# 11Dof.net
KiCad netlist of a schematic drawn in EAGLE
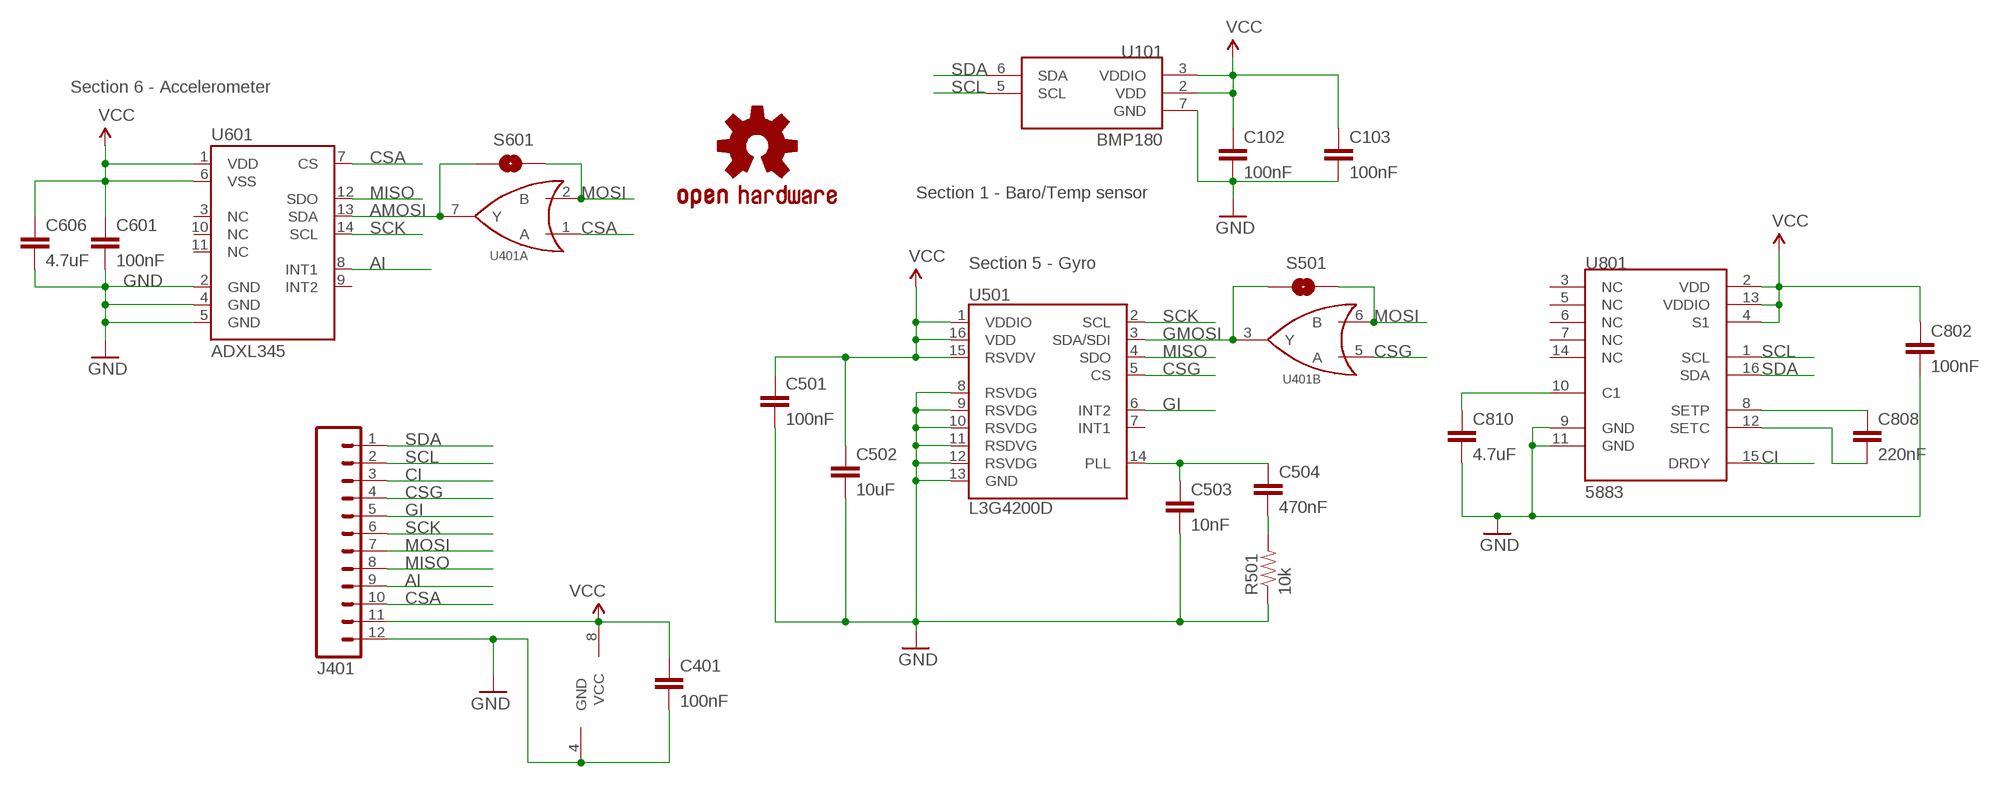
[diagram p0: schematic, sheet 1]

(export (version "E")
  (design (tool "Eeschema 10.0.6"))
  (components
    (comp (ref "C102")
      (value "100nF")
      (footprint "eagle-import:0603-CAP")
      (libsource (lib "eagle-import") (part "CAP0603-CAP"))
    )
    (comp (ref "C103")
      (value "100nF")
      (footprint "eagle-import:0603-CAP")
      (libsource (lib "eagle-import") (part "CAP0603-CAP"))
    )
    (comp (ref "C401")
      (value "100nF")
      (footprint "eagle-import:0603-CAP")
      (libsource (lib "eagle-import") (part "CAP0603-CAP"))
    )
    (comp (ref "C501")
      (value "100nF")
      (footprint "eagle-import:0603-CAP")
      (libsource (lib "eagle-import") (part "CAP0603-CAP"))
    )
    (comp (ref "C502")
      (value "10uF")
      (footprint "eagle-import:0603-CAP")
      (libsource (lib "eagle-import") (part "CAP0603-CAP"))
    )
    (comp (ref "C503")
      (value "10nF")
      (footprint "eagle-import:0603-CAP")
      (libsource (lib "eagle-import") (part "CAP0603-CAP"))
    )
    (comp (ref "C504")
      (value "470nF")
      (footprint "eagle-import:0603-CAP")
      (libsource (lib "eagle-import") (part "CAP0603-CAP"))
    )
    (comp (ref "C601")
      (value "100nF")
      (footprint "eagle-import:0603-CAP")
      (libsource (lib "eagle-import") (part "CAP0603-CAP"))
    )
    (comp (ref "C606")
      (value "4.7uF")
      (footprint "eagle-import:0603-CAP")
      (libsource (lib "eagle-import") (part "CAP0603-CAP"))
    )
    (comp (ref "C802")
      (value "100nF")
      (footprint "eagle-import:0603-CAP")
      (libsource (lib "eagle-import") (part "CAP0603-CAP"))
    )
    (comp (ref "C808")
      (value "220nF")
      (footprint "eagle-import:0603-CAP")
      (libsource (lib "eagle-import") (part "CAP0603-CAP"))
    )
    (comp (ref "C810")
      (value "4.7uF")
      (footprint "eagle-import:0603-CAP")
      (libsource (lib "eagle-import") (part "CAP0603-CAP"))
    )
    (comp (ref "J401")
      (value "M12PTH")
      (footprint "eagle-import:1X12")
      (libsource (lib "eagle-import") (part "M12PTH"))
    )
    (comp (ref "R501")
      (value "10k")
      (footprint "eagle-import:0603-RES")
      (libsource (lib "eagle-import") (part "RESISTOR0603-RES"))
    )
    (comp (ref "S501")
      (value "SOLDERJUMPERNO")
      (footprint "eagle-import:SJ_2S-NO")
      (libsource (lib "eagle-import") (part "SOLDERJUMPERNO"))
    )
    (comp (ref "S601")
      (value "SOLDERJUMPERNO")
      (footprint "eagle-import:SJ_2S-NO")
      (libsource (lib "eagle-import") (part "SOLDERJUMPERNO"))
    )
    (comp (ref "U$2")
      (value "OSHW-LOGOS")
      (footprint "eagle-import:OSHW-LOGO-S")
      (libsource (lib "eagle-import") (part "OSHW-LOGOS"))
    )
    (comp (ref "U101")
      (value "BMP180")
      (footprint "eagle-import:BMP180")
      (libsource (lib "eagle-import") (part "BMP180"))
    )
    (comp (ref "U401")
      (value "7432")
      (footprint "eagle-import:DCU_8")
      (fields (field (name "DIGIKEY") "296-13268-1-ND"))
      (libsource (lib "eagle-import") (part "SN74LVC2G32"))
    )
    (comp (ref "U501")
      (value "L3G4200D")
      (footprint "eagle-import:LGA16-4X4")
      (libsource (lib "eagle-import") (part "L3G4200D"))
    )
    (comp (ref "U601")
      (value "ADXL345")
      (footprint "eagle-import:LGA14")
      (libsource (lib "eagle-import") (part "ADXL345"))
    )
    (comp (ref "U801")
      (value "5883")
      (footprint "eagle-import:16LPCC")
      (libsource (lib "eagle-import") (part "HMC5883LSMD"))
    )
  )
  (nets
    (net (code "1") (name "/AI") (class "Default")
      (node (ref "J401") (pin "9") (pinfunction "9_9") (pintype "passive"))
      (node (ref "U601") (pin "8") (pinfunction "INT1_8") (pintype "bidirectional"))
    )
    (net (code "2") (name "/AMOSI") (class "Default")
      (node (ref "S601") (pin "1") (pinfunction "1_1") (pintype "passive"))
      (node (ref "U401") (pin "7") (pinfunction "Y_7") (pintype "bidirectional"))
      (node (ref "U601") (pin "13") (pinfunction "SDA_13") (pintype "bidirectional"))
    )
    (net (code "3") (name "/CI") (class "Default")
      (node (ref "J401") (pin "3") (pinfunction "3_3") (pintype "passive"))
      (node (ref "U801") (pin "15") (pinfunction "DRDY_15") (pintype "bidirectional"))
    )
    (net (code "4") (name "/CSA") (class "Default")
      (node (ref "J401") (pin "10") (pinfunction "10_10") (pintype "passive"))
      (node (ref "U401") (pin "1") (pinfunction "A_1") (pintype "bidirectional"))
      (node (ref "U601") (pin "7") (pinfunction "CS_7") (pintype "bidirectional"))
    )
    (net (code "5") (name "/CSG") (class "Default")
      (node (ref "J401") (pin "4") (pinfunction "4_4") (pintype "passive"))
      (node (ref "U401") (pin "5") (pinfunction "A_5") (pintype "bidirectional"))
      (node (ref "U501") (pin "5") (pinfunction "CS_5") (pintype "bidirectional"))
    )
    (net (code "6") (name "/GI") (class "Default")
      (node (ref "J401") (pin "5") (pinfunction "5_5") (pintype "passive"))
      (node (ref "U501") (pin "6") (pinfunction "INT2_6") (pintype "bidirectional"))
    )
    (net (code "7") (name "/GMOSI") (class "Default")
      (node (ref "S501") (pin "1") (pinfunction "1_1") (pintype "passive"))
      (node (ref "U401") (pin "3") (pinfunction "Y_3") (pintype "bidirectional"))
      (node (ref "U501") (pin "3") (pinfunction "SDA/SDI_3") (pintype "bidirectional"))
    )
    (net (code "8") (name "/MISO") (class "Default")
      (node (ref "J401") (pin "8") (pinfunction "8_8") (pintype "passive"))
      (node (ref "U501") (pin "4") (pinfunction "SDO_4") (pintype "bidirectional"))
      (node (ref "U601") (pin "12") (pinfunction "SDO_12") (pintype "bidirectional"))
    )
    (net (code "9") (name "/MOSI") (class "Default")
      (node (ref "J401") (pin "7") (pinfunction "7_7") (pintype "passive"))
      (node (ref "S501") (pin "2") (pinfunction "2_2") (pintype "passive"))
      (node (ref "S601") (pin "2") (pinfunction "2_2") (pintype "passive"))
      (node (ref "U401") (pin "2") (pinfunction "B_2") (pintype "bidirectional"))
      (node (ref "U401") (pin "6") (pinfunction "B_6") (pintype "bidirectional"))
    )
    (net (code "10") (name "/SCK") (class "Default")
      (node (ref "J401") (pin "6") (pinfunction "6_6") (pintype "passive"))
      (node (ref "U501") (pin "2") (pinfunction "SCL_2") (pintype "bidirectional"))
      (node (ref "U601") (pin "14") (pinfunction "SCL_14") (pintype "bidirectional"))
    )
    (net (code "11") (name "/SCL") (class "Default")
      (node (ref "J401") (pin "2") (pinfunction "2_2") (pintype "passive"))
      (node (ref "U101") (pin "5") (pinfunction "SCL_5") (pintype "input"))
      (node (ref "U801") (pin "1") (pinfunction "SCL_1") (pintype "bidirectional"))
    )
    (net (code "12") (name "/SDA") (class "Default")
      (node (ref "J401") (pin "1") (pinfunction "1_1") (pintype "passive"))
      (node (ref "U101") (pin "6") (pinfunction "SDA_6") (pintype "bidirectional"))
      (node (ref "U801") (pin "16") (pinfunction "SDA_16") (pintype "bidirectional"))
    )
    (net (code "13") (name "GND") (class "Default")
      (node (ref "C102") (pin "2") (pinfunction "2_2") (pintype "passive"))
      (node (ref "C103") (pin "2") (pinfunction "2_2") (pintype "passive"))
      (node (ref "C401") (pin "2") (pinfunction "2_2") (pintype "passive"))
      (node (ref "C501") (pin "2") (pinfunction "2_2") (pintype "passive"))
      (node (ref "C502") (pin "2") (pinfunction "2_2") (pintype "passive"))
      (node (ref "C503") (pin "2") (pinfunction "2_2") (pintype "passive"))
      (node (ref "C601") (pin "2") (pinfunction "2_2") (pintype "passive"))
      (node (ref "C606") (pin "2") (pinfunction "2_2") (pintype "passive"))
      (node (ref "C802") (pin "2") (pinfunction "2_2") (pintype "passive"))
      (node (ref "C810") (pin "2") (pinfunction "2_2") (pintype "passive"))
      (node (ref "J401") (pin "12") (pinfunction "12_12") (pintype "passive"))
      (node (ref "R501") (pin "1") (pinfunction "1_1") (pintype "passive"))
      (node (ref "U101") (pin "7") (pinfunction "GND_7") (pintype "power_in"))
      (node (ref "U401") (pin "4") (pinfunction "GND_4") (pintype "bidirectional"))
      (node (ref "U501") (pin "10") (pinfunction "RSVDG_10") (pintype "bidirectional"))
      (node (ref "U501") (pin "11") (pinfunction "RSDVG_11") (pintype "bidirectional"))
      (node (ref "U501") (pin "12") (pinfunction "RSVDG_12") (pintype "bidirectional"))
      (node (ref "U501") (pin "13") (pinfunction "GND_13") (pintype "bidirectional"))
      (node (ref "U501") (pin "8") (pinfunction "RSVDG_8") (pintype "bidirectional"))
      (node (ref "U501") (pin "9") (pinfunction "RSVDG_9") (pintype "bidirectional"))
      (node (ref "U601") (pin "2") (pinfunction "GND_2") (pintype "bidirectional"))
      (node (ref "U601") (pin "4") (pinfunction "GND_4") (pintype "bidirectional"))
      (node (ref "U601") (pin "5") (pinfunction "GND_5") (pintype "bidirectional"))
      (node (ref "U801") (pin "11") (pinfunction "GND_11") (pintype "bidirectional"))
      (node (ref "U801") (pin "9") (pinfunction "GND_9") (pintype "bidirectional"))
    )
    (net (code "14") (name "Net-(C504-Pad2)") (class "Default")
      (node (ref "C504") (pin "2") (pinfunction "2_2") (pintype "passive"))
      (node (ref "R501") (pin "2") (pinfunction "2_2") (pintype "passive"))
    )
    (net (code "15") (name "Net-(U501-PLL)") (class "Default")
      (node (ref "C503") (pin "1") (pinfunction "1_1") (pintype "passive"))
      (node (ref "C504") (pin "1") (pinfunction "1_1") (pintype "passive"))
      (node (ref "U501") (pin "14") (pinfunction "PLL_14") (pintype "bidirectional"))
    )
    (net (code "16") (name "Net-(U801-C1)") (class "Default")
      (node (ref "C810") (pin "1") (pinfunction "1_1") (pintype "passive"))
      (node (ref "U801") (pin "10") (pinfunction "C1_10") (pintype "bidirectional"))
    )
    (net (code "17") (name "Net-(U801-SETC)") (class "Default")
      (node (ref "C808") (pin "2") (pinfunction "2_2") (pintype "passive"))
      (node (ref "U801") (pin "12") (pinfunction "SETC_12") (pintype "bidirectional"))
    )
    (net (code "18") (name "Net-(U801-SETP)") (class "Default")
      (node (ref "C808") (pin "1") (pinfunction "1_1") (pintype "passive"))
      (node (ref "U801") (pin "8") (pinfunction "SETP_8") (pintype "bidirectional"))
    )
    (net (code "19") (name "VCC") (class "Default")
      (node (ref "C102") (pin "1") (pinfunction "1_1") (pintype "passive"))
      (node (ref "C103") (pin "1") (pinfunction "1_1") (pintype "passive"))
      (node (ref "C401") (pin "1") (pinfunction "1_1") (pintype "passive"))
      (node (ref "C501") (pin "1") (pinfunction "1_1") (pintype "passive"))
      (node (ref "C502") (pin "1") (pinfunction "1_1") (pintype "passive"))
      (node (ref "C601") (pin "1") (pinfunction "1_1") (pintype "passive"))
      (node (ref "C606") (pin "1") (pinfunction "1_1") (pintype "passive"))
      (node (ref "C802") (pin "1") (pinfunction "1_1") (pintype "passive"))
      (node (ref "J401") (pin "11") (pinfunction "11_11") (pintype "passive"))
      (node (ref "U101") (pin "2") (pinfunction "VDD_2") (pintype "power_in"))
      (node (ref "U101") (pin "3") (pinfunction "VDDIO_3") (pintype "power_in"))
      (node (ref "U401") (pin "8") (pinfunction "VCC_8") (pintype "bidirectional"))
      (node (ref "U501") (pin "1") (pinfunction "VDDIO_1") (pintype "bidirectional"))
      (node (ref "U501") (pin "15") (pinfunction "RSVDV_15") (pintype "bidirectional"))
      (node (ref "U501") (pin "16") (pinfunction "VDD_16") (pintype "bidirectional"))
      (node (ref "U601") (pin "1") (pinfunction "VDD_1") (pintype "bidirectional"))
      (node (ref "U601") (pin "6") (pinfunction "VSS_6") (pintype "bidirectional"))
      (node (ref "U801") (pin "13") (pinfunction "VDDIO_13") (pintype "bidirectional"))
      (node (ref "U801") (pin "2") (pinfunction "VDD_2") (pintype "bidirectional"))
      (node (ref "U801") (pin "4") (pinfunction "S1_4") (pintype "bidirectional"))
    )
    (net (code "20") (name "unconnected-(U501-INT1-Pad7)") (class "Default")
      (node (ref "U501") (pin "7") (pinfunction "INT1_7") (pintype "bidirectional"))
    )
    (net (code "21") (name "unconnected-(U601-INT2-Pad9)") (class "Default")
      (node (ref "U601") (pin "9") (pinfunction "INT2_9") (pintype "bidirectional"))
    )
    (net (code "22") (name "unconnected-(U601-NC-Pad3)") (class "Default")
      (node (ref "U601") (pin "3") (pinfunction "NC_3") (pintype "bidirectional"))
    )
    (net (code "23") (name "unconnected-(U601-NC-Pad10)") (class "Default")
      (node (ref "U601") (pin "10") (pinfunction "NC_10") (pintype "bidirectional"))
    )
    (net (code "24") (name "unconnected-(U601-NC-Pad11)") (class "Default")
      (node (ref "U601") (pin "11") (pinfunction "NC_11") (pintype "bidirectional"))
    )
    (net (code "25") (name "unconnected-(U801-NC-Pad3)") (class "Default")
      (node (ref "U801") (pin "3") (pinfunction "NC_3") (pintype "bidirectional"))
    )
    (net (code "26") (name "unconnected-(U801-NC-Pad5)") (class "Default")
      (node (ref "U801") (pin "5") (pinfunction "NC_5") (pintype "bidirectional"))
    )
    (net (code "27") (name "unconnected-(U801-NC-Pad6)") (class "Default")
      (node (ref "U801") (pin "6") (pinfunction "NC_6") (pintype "bidirectional"))
    )
    (net (code "28") (name "unconnected-(U801-NC-Pad7)") (class "Default")
      (node (ref "U801") (pin "7") (pinfunction "NC_7") (pintype "bidirectional"))
    )
    (net (code "29") (name "unconnected-(U801-NC-Pad14)") (class "Default")
      (node (ref "U801") (pin "14") (pinfunction "NC_14") (pintype "bidirectional"))
    )
  )
)
